# MCU.net
KiCad netlist of a schematic drawn in Altium Designer
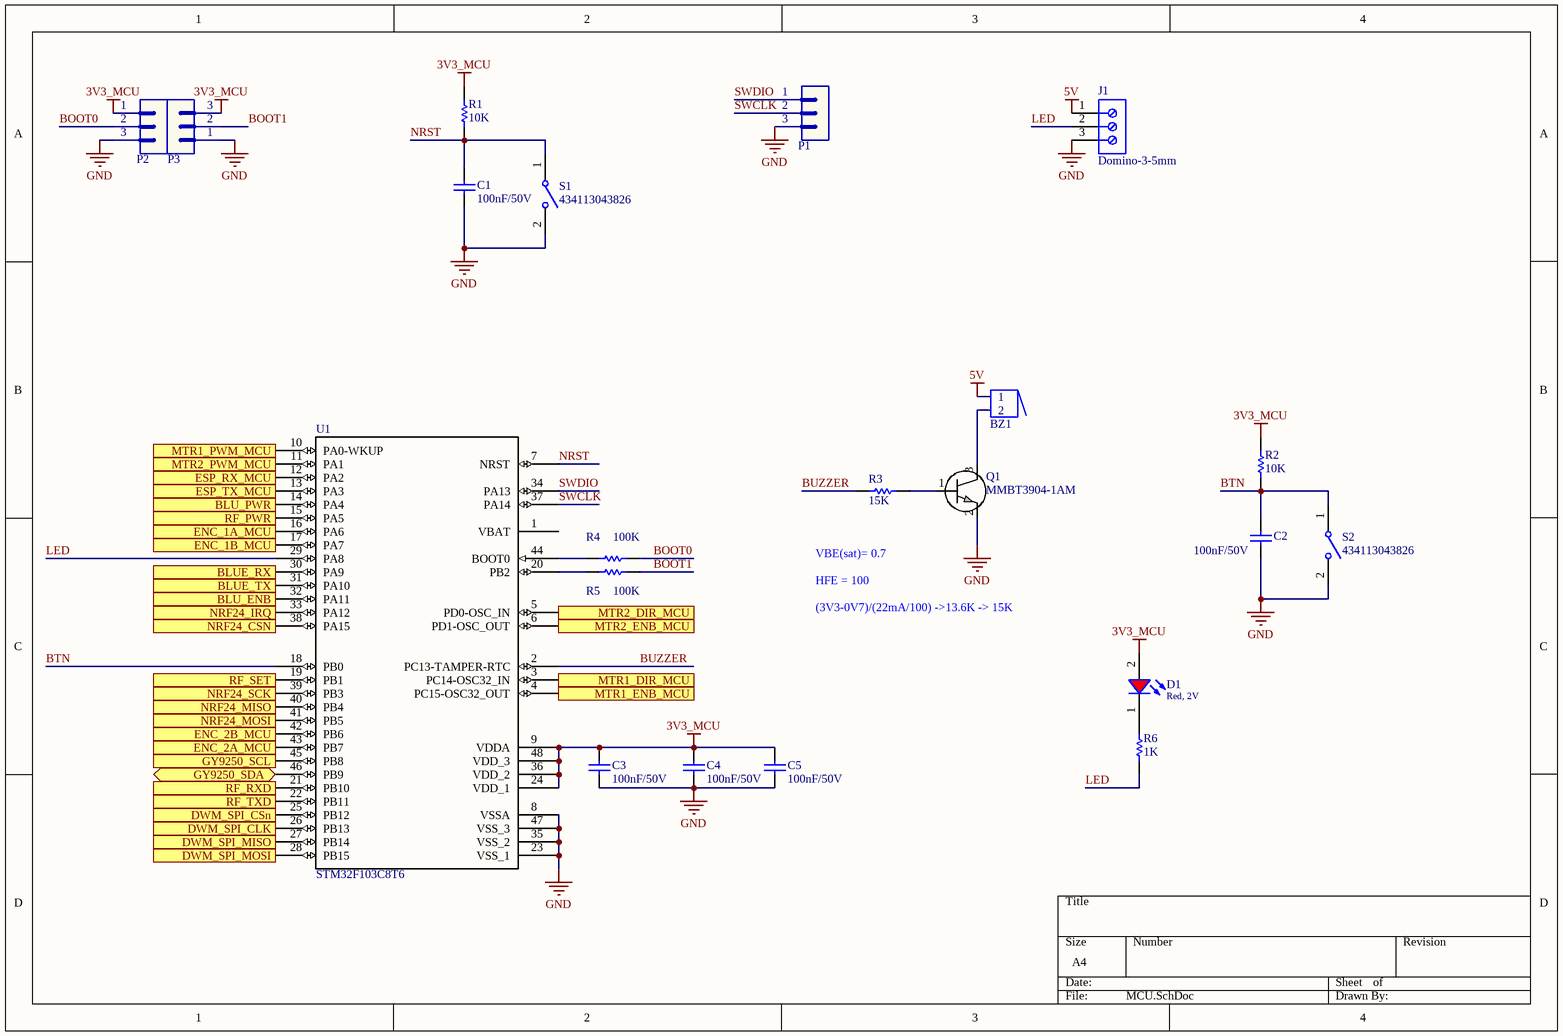
[diagram p0: MCU.SchDoc]

(export (version "E")
  (design (tool "Eeschema 10.0.6"))
  (components
    (comp (ref "BZ1") (value "Buzzer") (footprint "BUZZER") (libsource (lib "PIF_C16_lib") (part "Buzzer")))
    (comp (ref "C1")
      (value "100nF/50V")
      (footprint "CAP-SM-0805")
      (description "CAP CER 0.1UF 50V Y5V 0805")
      (fields
        (field (name "MANUFACTURER") "Samsung Electro-Mechanics")
        (field (name "MANUFACTURER PART NUMBER") "CL21F104ZBCNNNC")
      )
      (libsource (lib "Capacitor") (part "Cap-100nF-50V-0805"))
    )
    (comp (ref "C2")
      (value "100nF/50V")
      (footprint "CAP-SM-0805")
      (description "CAP CER 0.1UF 50V Y5V 0805")
      (fields
        (field (name "MANUFACTURER") "Samsung Electro-Mechanics")
        (field (name "MANUFACTURER PART NUMBER") "CL21F104ZBCNNNC")
      )
      (libsource (lib "Capacitor") (part "Cap-100nF-50V-0805"))
    )
    (comp (ref "C3")
      (value "100nF/50V")
      (footprint "CAP-SM-0805")
      (description "CAP CER 0.1UF 50V Y5V 0805")
      (fields
        (field (name "MANUFACTURER") "Samsung Electro-Mechanics")
        (field (name "MANUFACTURER PART NUMBER") "CL21F104ZBCNNNC")
      )
      (libsource (lib "Capacitor") (part "Cap-100nF-50V-0805"))
    )
    (comp (ref "C4")
      (value "100nF/50V")
      (footprint "CAP-SM-0805")
      (description "CAP CER 0.1UF 50V Y5V 0805")
      (fields
        (field (name "MANUFACTURER") "Samsung Electro-Mechanics")
        (field (name "MANUFACTURER PART NUMBER") "CL21F104ZBCNNNC")
      )
      (libsource (lib "Capacitor") (part "Cap-100nF-50V-0805"))
    )
    (comp (ref "C5")
      (value "100nF/50V")
      (footprint "CAP-SM-0805")
      (description "CAP CER 0.1UF 50V Y5V 0805")
      (fields
        (field (name "MANUFACTURER") "Samsung Electro-Mechanics")
        (field (name "MANUFACTURER PART NUMBER") "CL21F104ZBCNNNC")
      )
      (libsource (lib "Capacitor") (part "Cap-100nF-50V-0805"))
    )
    (comp (ref "D1")
      (value "Red, 2V")
      (footprint "WL-SMCW_0805")
      (description "WL-SMCW SMT Mono-color Chip LED Waterclear, size 0805, Red, 2V, 140deg")
      (fields (field (name "PART NUMBER") "150080RS75000") (field (name "PUBLISHER") "Wurth Elektronik"))
      (libsource (lib "LED_GREEN") (part "150080RS75000"))
    )
    (comp (ref "J1")
      (value "Domino-3-5mm")
      (footprint "DOMINO-3-5mm")
      (description "WR-TBL Serie 1347 Horizontal Cable Entry, Pressure Clamp, pitch 5mm, 3p")
      (fields (field (name "PART NUMBER") "691134710003") (field (name "PUBLISHER") "Wurth Elektronik"))
      (libsource (lib "Header-connector") (part "Domino-3-5mm"))
    )
    (comp (ref "P1")
      (value "Header 3")
      (footprint "JP3")
      (description "Header, 3-Pin")
      (fields (field (name "PUBLISHER") "Altium Limited"))
      (libsource (lib "Header-connector") (part "Header 3"))
    )
    (comp (ref "P2")
      (value "Header 3")
      (footprint "JP3")
      (description "Header, 3-Pin")
      (fields (field (name "PUBLISHER") "Altium Limited"))
      (libsource (lib "Header-connector") (part "Header 3"))
    )
    (comp (ref "P3")
      (value "Header 3")
      (footprint "JP3")
      (description "Header, 3-Pin")
      (fields (field (name "PUBLISHER") "Altium Limited"))
      (libsource (lib "") (part "Header 3_1"))
    )
    (comp (ref "Q1")
      (value "MMBT3904-1AM")
      (footprint "SOT23_NEX")
      (fields
        (field (name "MANUFACTURER_PART_NUMBER") "MMBT3904")
        (field (name "COPYRIGHT") "Copyright (C) 2016 Accelerated Designs. All rights reserved")
      )
      (libsource (lib "xecanbang") (part "MMBT3904-1AM"))
    )
    (comp (ref "R1")
      (value "10K")
      (footprint "Resistor:RES-SM-0805")
      (description "RES 10K OHM 1% 1/4W 0805")
      (fields
        (field (name "MANUFACTURER") "Stackpole Electronics Inc")
        (field (name "MANUFACTURER PART NUMBER") "RNCP0805FTD10K0")
      )
      (libsource (lib "Resistor") (part "Res-10k-0805"))
    )
    (comp (ref "R2")
      (value "10K")
      (footprint "Resistor:RES-SM-0805")
      (description "RES 10K OHM 1% 1/4W 0805")
      (fields
        (field (name "MANUFACTURER") "Stackpole Electronics Inc")
        (field (name "MANUFACTURER PART NUMBER") "RNCP0805FTD10K0")
      )
      (libsource (lib "Resistor") (part "Res-10k-0805"))
    )
    (comp (ref "R3")
      (value "15K")
      (footprint "Resistor:RES-SM-0805")
      (description "RES 15K OHM 1% 1/4W 0805")
      (fields
        (field (name "MANUFACTURER") "TE Connectivity Passive Product")
        (field (name "MANUFACTURER PART NUMBER") "CRGCQ0805F15K")
      )
      (libsource (lib "Resistor") (part "Res-15K-0805"))
    )
    (comp (ref "R4")
      (value "100K")
      (footprint "Resistor:RES-SM-0805")
      (description "RES 0 OHM JUMPER 0805")
      (fields
        (field (name "MANUFACTURER") "Vishay Dale")
        (field (name "MANUFACTURER PART NUMBER") "WSL080500000ZEA9")
      )
      (libsource (lib "Resistor") (part "Res-100K-0805"))
    )
    (comp (ref "R5")
      (value "100K")
      (footprint "Resistor:RES-SM-0805")
      (description "RES 0 OHM JUMPER 0805")
      (fields
        (field (name "MANUFACTURER") "Vishay Dale")
        (field (name "MANUFACTURER PART NUMBER") "WSL080500000ZEA9")
      )
      (libsource (lib "Resistor") (part "Res-100K-0805"))
    )
    (comp (ref "R6")
      (value "1K")
      (footprint "Resistor:RES-SM-0805")
      (description "RES 1K OHM 1% 1/4W 0805")
      (fields
        (field (name "MANUFACTURER") "Stackpole Electronics Inc")
        (field (name "MANUFACTURER PART NUMBER") "RNCP0805FTD1K00")
      )
      (libsource (lib "Resistor") (part "Res-1K-0805"))
    )
    (comp (ref "S1")
      (value "434113043826")
      (footprint "434113043826")
      (description "WS-TASV J-Bend SMT Tact Switch 6x3.5mm, height 4.3mm, 260gf")
      (fields (field (name "PUBLISHER") "Wurth Elektronik"))
      (libsource (lib "434123043816") (part "434113043826"))
    )
    (comp (ref "S2")
      (value "434113043826")
      (footprint "434113043826")
      (description "WS-TASV J-Bend SMT Tact Switch 6x3.5mm, height 4.3mm, 260gf")
      (fields (field (name "PUBLISHER") "Wurth Elektronik"))
      (libsource (lib "434123043816") (part "434113043826"))
    )
    (comp (ref "U1")
      (value "STM32F103C8T6")
      (footprint "STM32F103T8C6")
      (fields (field (name "COPYRIGHT") "Copyright (C) 2018 Accelerated Designs. All rights reserved"))
      (libsource (lib "xecanbang") (part "STM32F103C8T6"))
    )
  )
  (nets
    (net (code "1") (name "/BLUE_RX") (class "Default")
      (node (ref "U1") (pin "30") (pinfunction "PA9_30") (pintype "bidirectional"))
    )
    (net (code "2") (name "/BLUE_TX") (class "Default")
      (node (ref "U1") (pin "31") (pinfunction "PA10_31") (pintype "bidirectional"))
    )
    (net (code "3") (name "/BLU_ENB") (class "Default")
      (node (ref "U1") (pin "32") (pinfunction "PA11_32") (pintype "bidirectional"))
    )
    (net (code "4") (name "/BLU_PWR") (class "Default")
      (node (ref "U1") (pin "14") (pinfunction "PA4_14") (pintype "bidirectional"))
    )
    (net (code "5") (name "/BOOT0") (class "Default")
      (node (ref "P2") (pin "2") (pinfunction "2_2") (pintype "passive"))
      (node (ref "R4") (pin "2") (pinfunction "2_2") (pintype "passive"))
    )
    (net (code "6") (name "/BOOT1") (class "Default")
      (node (ref "P3") (pin "2") (pinfunction "2_2") (pintype "passive"))
      (node (ref "R5") (pin "2") (pinfunction "2_2") (pintype "passive"))
    )
    (net (code "7") (name "/BTN") (class "Default")
      (node (ref "C2") (pin "2") (pinfunction "2_2") (pintype "passive"))
      (node (ref "R2") (pin "1") (pinfunction "1_1") (pintype "passive"))
      (node (ref "S2") (pin "1") (pinfunction "1_1") (pintype "passive"))
      (node (ref "U1") (pin "18") (pinfunction "PB0_18") (pintype "bidirectional"))
    )
    (net (code "8") (name "/BUZZER") (class "Default")
      (node (ref "R3") (pin "1") (pinfunction "1_1") (pintype "passive"))
      (node (ref "U1") (pin "2") (pinfunction "PC13-TAMPER-RTC_2") (pintype "bidirectional"))
    )
    (net (code "9") (name "/DWM_SPI_CLK") (class "Default")
      (node (ref "U1") (pin "26") (pinfunction "PB13_26") (pintype "bidirectional"))
    )
    (net (code "10") (name "/DWM_SPI_CSn") (class "Default")
      (node (ref "U1") (pin "25") (pinfunction "PB12_25") (pintype "bidirectional"))
    )
    (net (code "11") (name "/DWM_SPI_MISO") (class "Default")
      (node (ref "U1") (pin "27") (pinfunction "PB14_27") (pintype "bidirectional"))
    )
    (net (code "12") (name "/DWM_SPI_MOSI") (class "Default")
      (node (ref "U1") (pin "28") (pinfunction "PB15_28") (pintype "bidirectional"))
    )
    (net (code "13") (name "/ENC_1A_MCU") (class "Default")
      (node (ref "U1") (pin "16") (pinfunction "PA6_16") (pintype "bidirectional"))
    )
    (net (code "14") (name "/ENC_1B_MCU") (class "Default")
      (node (ref "U1") (pin "17") (pinfunction "PA7_17") (pintype "bidirectional"))
    )
    (net (code "15") (name "/ENC_2A_MCU") (class "Default")
      (node (ref "U1") (pin "43") (pinfunction "PB7_43") (pintype "bidirectional"))
    )
    (net (code "16") (name "/ENC_2B_MCU") (class "Default")
      (node (ref "U1") (pin "42") (pinfunction "PB6_42") (pintype "bidirectional"))
    )
    (net (code "17") (name "/ESP_RX_MCU") (class "Default")
      (node (ref "U1") (pin "12") (pinfunction "PA2_12") (pintype "bidirectional"))
    )
    (net (code "18") (name "/ESP_TX_MCU") (class "Default")
      (node (ref "U1") (pin "13") (pinfunction "PA3_13") (pintype "bidirectional"))
    )
    (net (code "19") (name "/GY9250_SCL") (class "Default")
      (node (ref "U1") (pin "45") (pinfunction "PB8_45") (pintype "bidirectional"))
    )
    (net (code "20") (name "/GY9250_SDA") (class "Default")
      (node (ref "U1") (pin "46") (pinfunction "PB9_46") (pintype "bidirectional"))
    )
    (net (code "21") (name "/LED") (class "Default")
      (node (ref "J1") (pin "2") (pinfunction "2_2") (pintype "passive"))
      (node (ref "R6") (pin "2") (pinfunction "2_2") (pintype "passive"))
      (node (ref "U1") (pin "29") (pinfunction "PA8_29") (pintype "bidirectional"))
    )
    (net (code "22") (name "/MTR1_DIR_MCU") (class "Default")
      (node (ref "U1") (pin "3") (pinfunction "PC14-OSC32_IN_3") (pintype "bidirectional"))
    )
    (net (code "23") (name "/MTR1_ENB_MCU") (class "Default")
      (node (ref "U1") (pin "4") (pinfunction "PC15-OSC32_OUT_4") (pintype "bidirectional"))
    )
    (net (code "24") (name "/MTR1_PWM_MCU") (class "Default")
      (node (ref "U1") (pin "10") (pinfunction "PA0-WKUP_10") (pintype "bidirectional"))
    )
    (net (code "25") (name "/MTR2_DIR_MCU") (class "Default")
      (node (ref "U1") (pin "5") (pinfunction "PD0-OSC_IN_5") (pintype "bidirectional"))
    )
    (net (code "26") (name "/MTR2_ENB_MCU") (class "Default")
      (node (ref "U1") (pin "6") (pinfunction "PD1-OSC_OUT_6") (pintype "bidirectional"))
    )
    (net (code "27") (name "/MTR2_PWM_MCU") (class "Default")
      (node (ref "U1") (pin "11") (pinfunction "PA1_11") (pintype "bidirectional"))
    )
    (net (code "28") (name "/NRF24_CSN") (class "Default")
      (node (ref "U1") (pin "38") (pinfunction "PA15_38") (pintype "bidirectional"))
    )
    (net (code "29") (name "/NRF24_IRQ") (class "Default")
      (node (ref "U1") (pin "33") (pinfunction "PA12_33") (pintype "bidirectional"))
    )
    (net (code "30") (name "/NRF24_MISO") (class "Default")
      (node (ref "U1") (pin "40") (pinfunction "PB4_40") (pintype "bidirectional"))
    )
    (net (code "31") (name "/NRF24_MOSI") (class "Default")
      (node (ref "U1") (pin "41") (pinfunction "PB5_41") (pintype "bidirectional"))
    )
    (net (code "32") (name "/NRF24_SCK") (class "Default")
      (node (ref "U1") (pin "39") (pinfunction "PB3_39") (pintype "bidirectional"))
    )
    (net (code "33") (name "/NRST") (class "Default")
      (node (ref "C1") (pin "2") (pinfunction "2_2") (pintype "passive"))
      (node (ref "R1") (pin "2") (pinfunction "2_2") (pintype "passive"))
      (node (ref "S1") (pin "1") (pinfunction "1_1") (pintype "passive"))
      (node (ref "U1") (pin "7") (pinfunction "NRST_7") (pintype "bidirectional"))
    )
    (net (code "34") (name "/RF_PWR") (class "Default")
      (node (ref "U1") (pin "15") (pinfunction "PA5_15") (pintype "bidirectional"))
    )
    (net (code "35") (name "/RF_RXD") (class "Default")
      (node (ref "U1") (pin "21") (pinfunction "PB10_21") (pintype "bidirectional"))
    )
    (net (code "36") (name "/RF_SET") (class "Default")
      (node (ref "U1") (pin "19") (pinfunction "PB1_19") (pintype "bidirectional"))
    )
    (net (code "37") (name "/RF_TXD") (class "Default")
      (node (ref "U1") (pin "22") (pinfunction "PB11_22") (pintype "bidirectional"))
    )
    (net (code "38") (name "/SWCLK") (class "Default")
      (node (ref "P1") (pin "2") (pinfunction "2_2") (pintype "passive"))
      (node (ref "U1") (pin "37") (pinfunction "PA14_37") (pintype "bidirectional"))
    )
    (net (code "39") (name "/SWDIO") (class "Default")
      (node (ref "P1") (pin "1") (pinfunction "1_1") (pintype "passive"))
      (node (ref "U1") (pin "34") (pinfunction "PA13_34") (pintype "bidirectional"))
    )
    (net (code "40") (name "3V3_MCU") (class "Default")
      (node (ref "C3") (pin "1") (pinfunction "1_1") (pintype "passive"))
      (node (ref "C4") (pin "1") (pinfunction "1_1") (pintype "passive"))
      (node (ref "C5") (pin "1") (pinfunction "1_1") (pintype "passive"))
      (node (ref "D1") (pin "2") (pinfunction "A_2") (pintype "passive"))
      (node (ref "P2") (pin "1") (pinfunction "1_1") (pintype "passive"))
      (node (ref "P3") (pin "3") (pinfunction "3_3") (pintype "passive"))
      (node (ref "R1") (pin "1") (pinfunction "1_1") (pintype "passive"))
      (node (ref "R2") (pin "2") (pinfunction "2_2") (pintype "passive"))
      (node (ref "U1") (pin "24") (pinfunction "VDD_1_24") (pintype "power_in"))
      (node (ref "U1") (pin "36") (pinfunction "VDD_2_36") (pintype "power_in"))
      (node (ref "U1") (pin "48") (pinfunction "VDD_3_48") (pintype "power_in"))
      (node (ref "U1") (pin "9") (pinfunction "VDDA_9") (pintype "power_in"))
    )
    (net (code "41") (name "5V") (class "Default")
      (node (ref "BZ1") (pin "1") (pinfunction "1_1") (pintype "passive"))
      (node (ref "J1") (pin "1") (pinfunction "1_1") (pintype "passive"))
    )
    (net (code "42") (name "GND") (class "Default")
      (node (ref "C1") (pin "1") (pinfunction "1_1") (pintype "passive"))
      (node (ref "C2") (pin "1") (pinfunction "1_1") (pintype "passive"))
      (node (ref "C3") (pin "2") (pinfunction "2_2") (pintype "passive"))
      (node (ref "C4") (pin "2") (pinfunction "2_2") (pintype "passive"))
      (node (ref "C5") (pin "2") (pinfunction "2_2") (pintype "passive"))
      (node (ref "J1") (pin "3") (pinfunction "3_3") (pintype "passive"))
      (node (ref "P1") (pin "3") (pinfunction "3_3") (pintype "passive"))
      (node (ref "P2") (pin "3") (pinfunction "3_3") (pintype "passive"))
      (node (ref "P3") (pin "1") (pinfunction "1_1") (pintype "passive"))
      (node (ref "Q1") (pin "2") (pinfunction "2_2") (pintype "passive"))
      (node (ref "S1") (pin "2") (pinfunction "2_2") (pintype "passive"))
      (node (ref "S2") (pin "2") (pinfunction "2_2") (pintype "passive"))
      (node (ref "U1") (pin "23") (pinfunction "VSS_1_23") (pintype "power_in"))
      (node (ref "U1") (pin "35") (pinfunction "VSS_2_35") (pintype "power_in"))
      (node (ref "U1") (pin "47") (pinfunction "VSS_3_47") (pintype "power_in"))
      (node (ref "U1") (pin "8") (pinfunction "VSSA_8") (pintype "power_in"))
    )
    (net (code "43") (name "Net-(BZ1-Pad2)") (class "Default")
      (node (ref "BZ1") (pin "2") (pinfunction "2_2") (pintype "passive"))
      (node (ref "Q1") (pin "3") (pinfunction "3_3") (pintype "passive"))
    )
    (net (code "44") (name "Net-(D1-K)") (class "Default")
      (node (ref "D1") (pin "1") (pinfunction "K_1") (pintype "passive"))
      (node (ref "R6") (pin "1") (pinfunction "1_1") (pintype "passive"))
    )
    (net (code "45") (name "Net-(Q1-Pad1)") (class "Default")
      (node (ref "Q1") (pin "1") (pinfunction "1_1") (pintype "passive"))
      (node (ref "R3") (pin "2") (pinfunction "2_2") (pintype "passive"))
    )
    (net (code "46") (name "Net-(U1-BOOT0)") (class "Default")
      (node (ref "R4") (pin "1") (pinfunction "1_1") (pintype "passive"))
      (node (ref "U1") (pin "44") (pinfunction "BOOT0_44") (pintype "input"))
    )
    (net (code "47") (name "Net-(U1-PB2)") (class "Default")
      (node (ref "R5") (pin "1") (pinfunction "1_1") (pintype "passive"))
      (node (ref "U1") (pin "20") (pinfunction "PB2_20") (pintype "bidirectional"))
    )
    (net (code "48") (name "unconnected-(U1-VBAT-Pad1)") (class "Default")
      (node (ref "U1") (pin "1") (pinfunction "VBAT_1") (pintype "power_in"))
    )
  )
)
